# motherboard.net
KiCad netlist of a schematic drawn in EAGLE
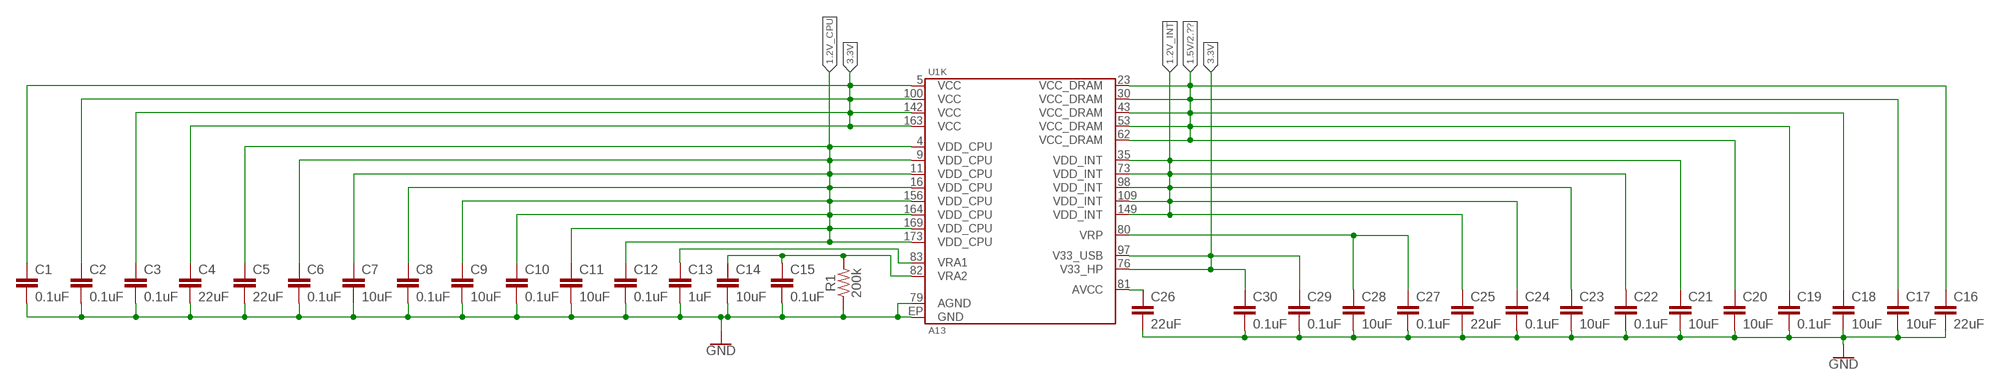
[diagram p0: schematic, sheet 1]
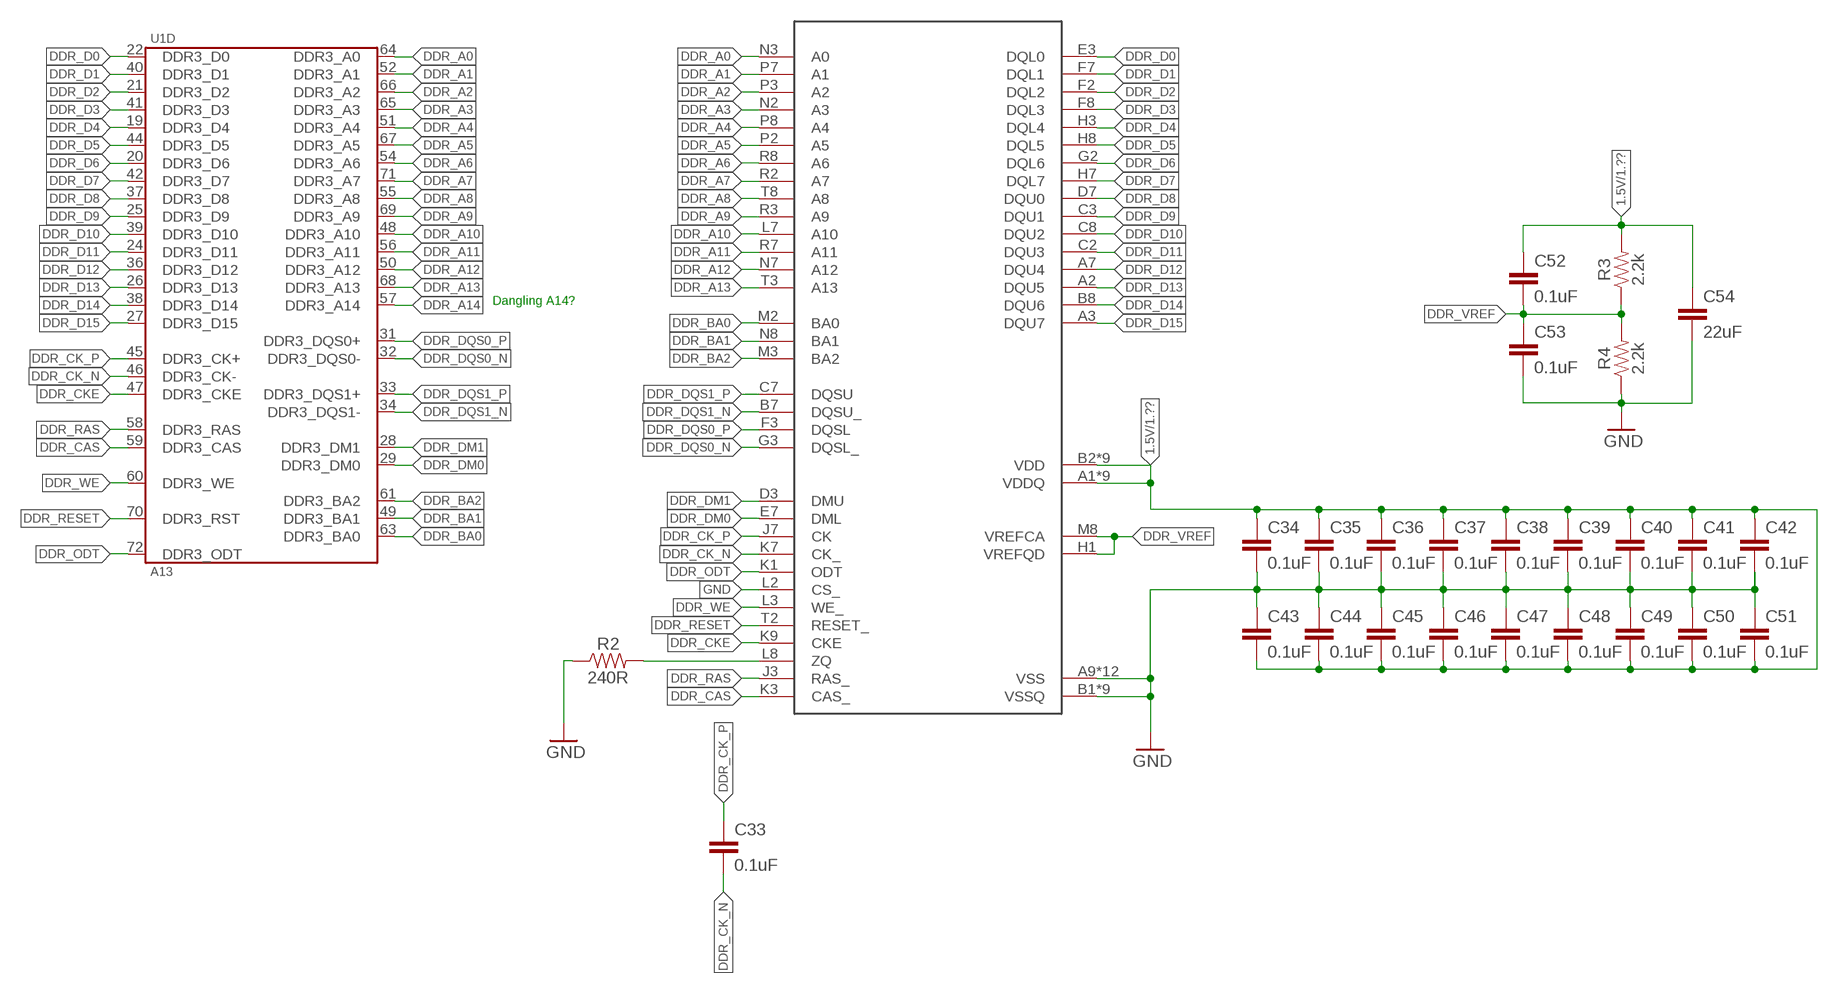
[diagram p1: schematic, sheet 2]
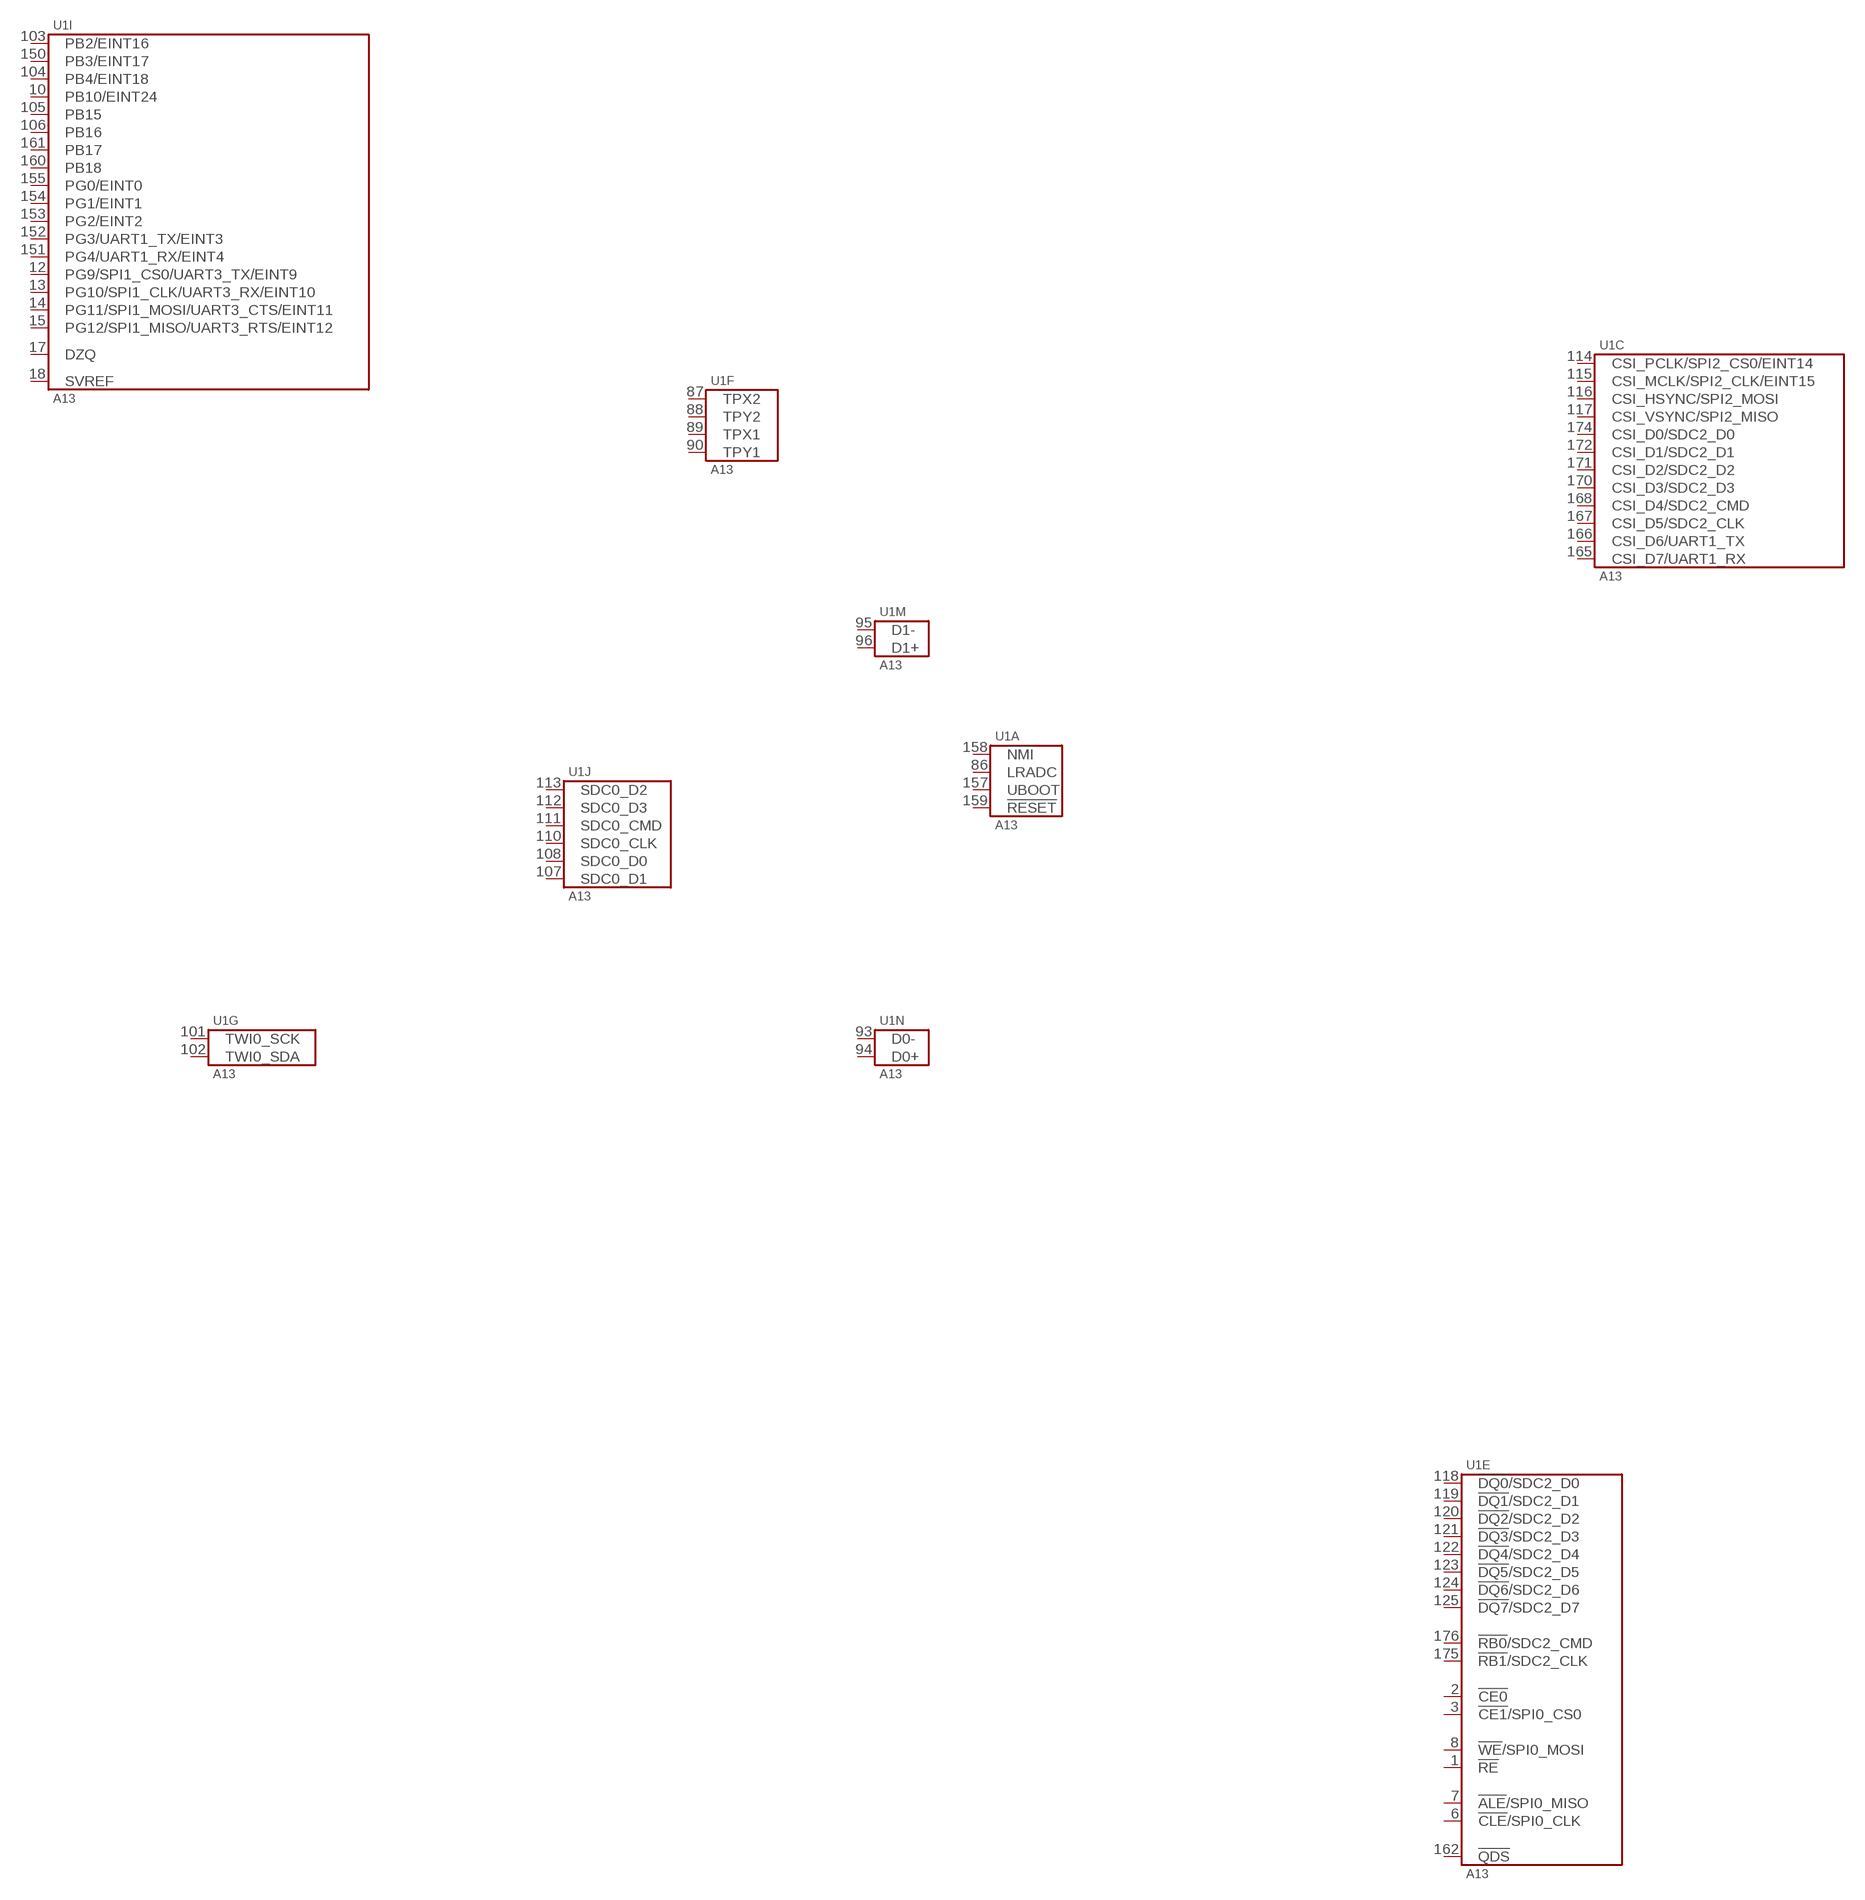
[diagram p2: schematic, sheet 5]
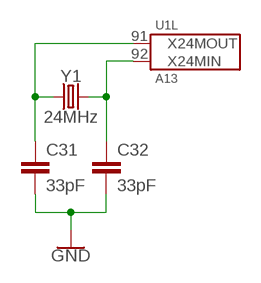
[diagram p3: schematic, sheet 6]

(export (version "E")
  (design (tool "Eeschema 10.0.6"))
  (components
    (comp (ref "C1")
      (value "0.1uF")
      (footprint "eagle-import:0603")
      (libsource (lib "eagle-import") (part "0.1UF-0603-25V-(+80/-20%)"))
    )
    (comp (ref "C2")
      (value "0.1uF")
      (footprint "eagle-import:0603")
      (libsource (lib "eagle-import") (part "0.1UF-0603-25V-(+80/-20%)"))
    )
    (comp (ref "C3")
      (value "0.1uF")
      (footprint "eagle-import:0603")
      (libsource (lib "eagle-import") (part "0.1UF-0603-25V-(+80/-20%)"))
    )
    (comp (ref "C4")
      (value "22uF")
      (footprint "eagle-import:0603")
      (libsource (lib "eagle-import") (part "0.1UF-0603-25V-(+80/-20%)"))
    )
    (comp (ref "C5")
      (value "22uF")
      (footprint "eagle-import:0603")
      (libsource (lib "eagle-import") (part "0.1UF-0603-25V-(+80/-20%)"))
    )
    (comp (ref "C6")
      (value "0.1uF")
      (footprint "eagle-import:0603")
      (libsource (lib "eagle-import") (part "0.1UF-0603-25V-(+80/-20%)"))
    )
    (comp (ref "C7")
      (value "10uF")
      (footprint "eagle-import:0603")
      (libsource (lib "eagle-import") (part "0.1UF-0603-25V-(+80/-20%)"))
    )
    (comp (ref "C8")
      (value "0.1uF")
      (footprint "eagle-import:0603")
      (libsource (lib "eagle-import") (part "0.1UF-0603-25V-(+80/-20%)"))
    )
    (comp (ref "C9")
      (value "10uF")
      (footprint "eagle-import:0603")
      (libsource (lib "eagle-import") (part "0.1UF-0603-25V-(+80/-20%)"))
    )
    (comp (ref "C10")
      (value "0.1uF")
      (footprint "eagle-import:0603")
      (libsource (lib "eagle-import") (part "0.1UF-0603-25V-(+80/-20%)"))
    )
    (comp (ref "C11")
      (value "10uF")
      (footprint "eagle-import:0603")
      (libsource (lib "eagle-import") (part "0.1UF-0603-25V-(+80/-20%)"))
    )
    (comp (ref "C12")
      (value "0.1uF")
      (footprint "eagle-import:0603")
      (libsource (lib "eagle-import") (part "0.1UF-0603-25V-(+80/-20%)"))
    )
    (comp (ref "C13")
      (value "1uF")
      (footprint "eagle-import:0603")
      (libsource (lib "eagle-import") (part "0.1UF-0603-25V-(+80/-20%)"))
    )
    (comp (ref "C14")
      (value "10uF")
      (footprint "eagle-import:0603")
      (libsource (lib "eagle-import") (part "0.1UF-0603-25V-(+80/-20%)"))
    )
    (comp (ref "C15")
      (value "0.1uF")
      (footprint "eagle-import:0603")
      (libsource (lib "eagle-import") (part "0.1UF-0603-25V-(+80/-20%)"))
    )
    (comp (ref "C16")
      (value "22uF")
      (footprint "eagle-import:0603")
      (libsource (lib "eagle-import") (part "0.1UF-0603-25V-(+80/-20%)"))
    )
    (comp (ref "C17")
      (value "10uF")
      (footprint "eagle-import:0603")
      (libsource (lib "eagle-import") (part "0.1UF-0603-25V-(+80/-20%)"))
    )
    (comp (ref "C18")
      (value "10uF")
      (footprint "eagle-import:0603")
      (libsource (lib "eagle-import") (part "0.1UF-0603-25V-(+80/-20%)"))
    )
    (comp (ref "C19")
      (value "0.1uF")
      (footprint "eagle-import:0603")
      (libsource (lib "eagle-import") (part "0.1UF-0603-25V-(+80/-20%)"))
    )
    (comp (ref "C20")
      (value "10uF")
      (footprint "eagle-import:0603")
      (libsource (lib "eagle-import") (part "0.1UF-0603-25V-(+80/-20%)"))
    )
    (comp (ref "C21")
      (value "10uF")
      (footprint "eagle-import:0603")
      (libsource (lib "eagle-import") (part "0.1UF-0603-25V-(+80/-20%)"))
    )
    (comp (ref "C22")
      (value "0.1uF")
      (footprint "eagle-import:0603")
      (libsource (lib "eagle-import") (part "0.1UF-0603-25V-(+80/-20%)"))
    )
    (comp (ref "C23")
      (value "10uF")
      (footprint "eagle-import:0603")
      (libsource (lib "eagle-import") (part "0.1UF-0603-25V-(+80/-20%)"))
    )
    (comp (ref "C24")
      (value "0.1uF")
      (footprint "eagle-import:0603")
      (libsource (lib "eagle-import") (part "0.1UF-0603-25V-(+80/-20%)"))
    )
    (comp (ref "C25")
      (value "22uF")
      (footprint "eagle-import:0603")
      (libsource (lib "eagle-import") (part "0.1UF-0603-25V-(+80/-20%)"))
    )
    (comp (ref "C26")
      (value "22uF")
      (footprint "eagle-import:0603")
      (libsource (lib "eagle-import") (part "0.1UF-0603-25V-(+80/-20%)"))
    )
    (comp (ref "C27")
      (value "0.1uF")
      (footprint "eagle-import:0603")
      (libsource (lib "eagle-import") (part "0.1UF-0603-25V-(+80/-20%)"))
    )
    (comp (ref "C28")
      (value "10uF")
      (footprint "eagle-import:0603")
      (libsource (lib "eagle-import") (part "0.1UF-0603-25V-(+80/-20%)"))
    )
    (comp (ref "C29")
      (value "0.1uF")
      (footprint "eagle-import:0603")
      (libsource (lib "eagle-import") (part "0.1UF-0603-25V-(+80/-20%)"))
    )
    (comp (ref "C30")
      (value "0.1uF")
      (footprint "eagle-import:0603")
      (libsource (lib "eagle-import") (part "0.1UF-0603-25V-(+80/-20%)"))
    )
    (comp (ref "R1")
      (value "200k")
      (footprint "eagle-import:0603")
      (libsource (lib "eagle-import") (part "200KOHM-0603-1/10W-1%"))
    )
    (comp (ref "U1")
      (value "A13")
      (footprint "eagle-import:A13")
      (libsource (lib "eagle-import") (part "A13"))
    )
    (comp (ref "C33")
      (value "0.1uF")
      (footprint "eagle-import:0603")
      (libsource (lib "eagle-import") (part "0.1UF-0603-25V-(+80/-20%)"))
    )
    (comp (ref "C34")
      (value "0.1uF")
      (footprint "eagle-import:0603")
      (libsource (lib "eagle-import") (part "0.1UF-0603-25V-(+80/-20%)"))
    )
    (comp (ref "C35")
      (value "0.1uF")
      (footprint "eagle-import:0603")
      (libsource (lib "eagle-import") (part "0.1UF-0603-25V-(+80/-20%)"))
    )
    (comp (ref "C36")
      (value "0.1uF")
      (footprint "eagle-import:0603")
      (libsource (lib "eagle-import") (part "0.1UF-0603-25V-(+80/-20%)"))
    )
    (comp (ref "C37")
      (value "0.1uF")
      (footprint "eagle-import:0603")
      (libsource (lib "eagle-import") (part "0.1UF-0603-25V-(+80/-20%)"))
    )
    (comp (ref "C38")
      (value "0.1uF")
      (footprint "eagle-import:0603")
      (libsource (lib "eagle-import") (part "0.1UF-0603-25V-(+80/-20%)"))
    )
    (comp (ref "C39")
      (value "0.1uF")
      (footprint "eagle-import:0603")
      (libsource (lib "eagle-import") (part "0.1UF-0603-25V-(+80/-20%)"))
    )
    (comp (ref "C40")
      (value "0.1uF")
      (footprint "eagle-import:0603")
      (libsource (lib "eagle-import") (part "0.1UF-0603-25V-(+80/-20%)"))
    )
    (comp (ref "C41")
      (value "0.1uF")
      (footprint "eagle-import:0603")
      (libsource (lib "eagle-import") (part "0.1UF-0603-25V-(+80/-20%)"))
    )
    (comp (ref "C42")
      (value "0.1uF")
      (footprint "eagle-import:0603")
      (libsource (lib "eagle-import") (part "0.1UF-0603-25V-(+80/-20%)"))
    )
    (comp (ref "C43")
      (value "0.1uF")
      (footprint "eagle-import:0603")
      (libsource (lib "eagle-import") (part "0.1UF-0603-25V-(+80/-20%)"))
    )
    (comp (ref "C44")
      (value "0.1uF")
      (footprint "eagle-import:0603")
      (libsource (lib "eagle-import") (part "0.1UF-0603-25V-(+80/-20%)"))
    )
    (comp (ref "C45")
      (value "0.1uF")
      (footprint "eagle-import:0603")
      (libsource (lib "eagle-import") (part "0.1UF-0603-25V-(+80/-20%)"))
    )
    (comp (ref "C46")
      (value "0.1uF")
      (footprint "eagle-import:0603")
      (libsource (lib "eagle-import") (part "0.1UF-0603-25V-(+80/-20%)"))
    )
    (comp (ref "C47")
      (value "0.1uF")
      (footprint "eagle-import:0603")
      (libsource (lib "eagle-import") (part "0.1UF-0603-25V-(+80/-20%)"))
    )
    (comp (ref "C48")
      (value "0.1uF")
      (footprint "eagle-import:0603")
      (libsource (lib "eagle-import") (part "0.1UF-0603-25V-(+80/-20%)"))
    )
    (comp (ref "C49")
      (value "0.1uF")
      (footprint "eagle-import:0603")
      (libsource (lib "eagle-import") (part "0.1UF-0603-25V-(+80/-20%)"))
    )
    (comp (ref "C50")
      (value "0.1uF")
      (footprint "eagle-import:0603")
      (libsource (lib "eagle-import") (part "0.1UF-0603-25V-(+80/-20%)"))
    )
    (comp (ref "C51")
      (value "0.1uF")
      (footprint "eagle-import:0603")
      (libsource (lib "eagle-import") (part "0.1UF-0603-25V-(+80/-20%)"))
    )
    (comp (ref "C52")
      (value "0.1uF")
      (footprint "eagle-import:0603")
      (libsource (lib "eagle-import") (part "0.1UF-0603-25V-(+80/-20%)"))
    )
    (comp (ref "C53")
      (value "0.1uF")
      (footprint "eagle-import:0603")
      (libsource (lib "eagle-import") (part "0.1UF-0603-25V-(+80/-20%)"))
    )
    (comp (ref "C54")
      (value "22uF")
      (footprint "eagle-import:0603")
      (libsource (lib "eagle-import") (part "0.1UF-0603-25V-(+80/-20%)"))
    )
    (comp (ref "DRAM")
      (value "AS4C128M16D3B-12BCN")
      (footprint "eagle-import:FBGA96-6X16")
      (libsource (lib "eagle-import") (part "AS4C128M16D3B-12BCN"))
    )
    (comp (ref "R2")
      (value "240R")
      (footprint "eagle-import:0603")
      (libsource (lib "eagle-import") (part "200KOHM-0603-1/10W-1%"))
    )
    (comp (ref "R3")
      (value "2.2k")
      (footprint "eagle-import:0603")
      (libsource (lib "eagle-import") (part "200KOHM-0603-1/10W-1%"))
    )
    (comp (ref "R4")
      (value "2.2k")
      (footprint "eagle-import:0603")
      (libsource (lib "eagle-import") (part "200KOHM-0603-1/10W-1%"))
    )
    (comp (ref "C31")
      (value "33pF")
      (footprint "eagle-import:0603")
      (libsource (lib "eagle-import") (part "0.1UF-0603-25V-(+80/-20%)"))
    )
    (comp (ref "C32")
      (value "33pF")
      (footprint "eagle-import:0603")
      (libsource (lib "eagle-import") (part "0.1UF-0603-25V-(+80/-20%)"))
    )
    (comp (ref "Y1")
      (value "24MHz")
      (footprint "eagle-import:CRYSTAL-SMD-5X3.2-4PAD")
      (libsource (lib "eagle-import") (part "CRYSTAL-24MHZ{dblquote}"))
    )
  )
  (nets
    (net (code "1") (name "1.2V_CPU") (class "Default")
      (node (ref "C10") (pin "1") (pinfunction "1_1") (pintype "passive"))
      (node (ref "C11") (pin "1") (pinfunction "1_1") (pintype "passive"))
      (node (ref "C12") (pin "1") (pinfunction "1_1") (pintype "passive"))
      (node (ref "C5") (pin "1") (pinfunction "1_1") (pintype "passive"))
      (node (ref "C6") (pin "1") (pinfunction "1_1") (pintype "passive"))
      (node (ref "C7") (pin "1") (pinfunction "1_1") (pintype "passive"))
      (node (ref "C8") (pin "1") (pinfunction "1_1") (pintype "passive"))
      (node (ref "C9") (pin "1") (pinfunction "1_1") (pintype "passive"))
      (node (ref "U1") (pin "11") (pinfunction "VDD_CPU_11") (pintype "bidirectional"))
      (node (ref "U1") (pin "156") (pinfunction "VDD_CPU_156") (pintype "bidirectional"))
      (node (ref "U1") (pin "16") (pinfunction "VDD_CPU_16") (pintype "bidirectional"))
      (node (ref "U1") (pin "164") (pinfunction "VDD_CPU_164") (pintype "bidirectional"))
      (node (ref "U1") (pin "169") (pinfunction "VDD_CPU_169") (pintype "bidirectional"))
      (node (ref "U1") (pin "173") (pinfunction "VDD_CPU_173") (pintype "bidirectional"))
      (node (ref "U1") (pin "4") (pinfunction "VDD_CPU_4") (pintype "bidirectional"))
      (node (ref "U1") (pin "9") (pinfunction "VDD_CPU_9") (pintype "bidirectional"))
    )
    (net (code "2") (name "1.2V_INT") (class "Default")
      (node (ref "C21") (pin "1") (pinfunction "1_1") (pintype "passive"))
      (node (ref "C22") (pin "1") (pinfunction "1_1") (pintype "passive"))
      (node (ref "C23") (pin "1") (pinfunction "1_1") (pintype "passive"))
      (node (ref "C24") (pin "1") (pinfunction "1_1") (pintype "passive"))
      (node (ref "C25") (pin "1") (pinfunction "1_1") (pintype "passive"))
      (node (ref "U1") (pin "109") (pinfunction "VDD_INT_109") (pintype "bidirectional"))
      (node (ref "U1") (pin "149") (pinfunction "VDD_INT_149") (pintype "bidirectional"))
      (node (ref "U1") (pin "35") (pinfunction "VDD_INT_35") (pintype "bidirectional"))
      (node (ref "U1") (pin "73") (pinfunction "VDD_INT_73") (pintype "bidirectional"))
      (node (ref "U1") (pin "98") (pinfunction "VDD_INT_98") (pintype "bidirectional"))
    )
    (net (code "3") (name "1.5V") (class "Default")
      (node (ref "C16") (pin "1") (pinfunction "1_1") (pintype "passive"))
      (node (ref "C17") (pin "1") (pinfunction "1_1") (pintype "passive"))
      (node (ref "C18") (pin "1") (pinfunction "1_1") (pintype "passive"))
      (node (ref "C19") (pin "1") (pinfunction "1_1") (pintype "passive"))
      (node (ref "C20") (pin "1") (pinfunction "1_1") (pintype "passive"))
      (node (ref "C34") (pin "1") (pinfunction "1_1") (pintype "passive"))
      (node (ref "C35") (pin "1") (pinfunction "1_1") (pintype "passive"))
      (node (ref "C36") (pin "1") (pinfunction "1_1") (pintype "passive"))
      (node (ref "C37") (pin "1") (pinfunction "1_1") (pintype "passive"))
      (node (ref "C38") (pin "1") (pinfunction "1_1") (pintype "passive"))
      (node (ref "C39") (pin "1") (pinfunction "1_1") (pintype "passive"))
      (node (ref "C40") (pin "1") (pinfunction "1_1") (pintype "passive"))
      (node (ref "C41") (pin "1") (pinfunction "1_1") (pintype "passive"))
      (node (ref "C42") (pin "1") (pinfunction "1_1") (pintype "passive"))
      (node (ref "C43") (pin "2") (pinfunction "2_2") (pintype "passive"))
      (node (ref "C44") (pin "2") (pinfunction "2_2") (pintype "passive"))
      (node (ref "C45") (pin "2") (pinfunction "2_2") (pintype "passive"))
      (node (ref "C46") (pin "2") (pinfunction "2_2") (pintype "passive"))
      (node (ref "C47") (pin "2") (pinfunction "2_2") (pintype "passive"))
      (node (ref "C48") (pin "2") (pinfunction "2_2") (pintype "passive"))
      (node (ref "C49") (pin "2") (pinfunction "2_2") (pintype "passive"))
      (node (ref "C50") (pin "2") (pinfunction "2_2") (pintype "passive"))
      (node (ref "C51") (pin "2") (pinfunction "2_2") (pintype "passive"))
      (node (ref "C52") (pin "1") (pinfunction "1_1") (pintype "passive"))
      (node (ref "C54") (pin "1") (pinfunction "1_1") (pintype "passive"))
      (node (ref "DRAM") (pin "A1") (pinfunction "VDDQ_A1") (pintype "bidirectional"))
      (node (ref "DRAM") (pin "A8") (pinfunction "VDDQ_A8") (pintype "bidirectional"))
      (node (ref "DRAM") (pin "B2") (pinfunction "VDD_B2") (pintype "bidirectional"))
      (node (ref "DRAM") (pin "C1") (pinfunction "VDDQ_C1") (pintype "bidirectional"))
      (node (ref "DRAM") (pin "C9") (pinfunction "VDDQ_C9") (pintype "bidirectional"))
      (node (ref "DRAM") (pin "D2") (pinfunction "VDDQ_D2") (pintype "bidirectional"))
      (node (ref "DRAM") (pin "D9") (pinfunction "VDD_D9") (pintype "bidirectional"))
      (node (ref "DRAM") (pin "E9") (pinfunction "VDDQ_E9") (pintype "bidirectional"))
      (node (ref "DRAM") (pin "F1") (pinfunction "VDDQ_F1") (pintype "bidirectional"))
      (node (ref "DRAM") (pin "G7") (pinfunction "VDD_G7") (pintype "bidirectional"))
      (node (ref "DRAM") (pin "H2") (pinfunction "VDDQ_H2") (pintype "bidirectional"))
      (node (ref "DRAM") (pin "H9") (pinfunction "VDDQ_H9") (pintype "bidirectional"))
      (node (ref "DRAM") (pin "K2") (pinfunction "VDD_K2") (pintype "bidirectional"))
      (node (ref "DRAM") (pin "K8") (pinfunction "VDD_K8") (pintype "bidirectional"))
      (node (ref "DRAM") (pin "N1") (pinfunction "VDD_N1") (pintype "bidirectional"))
      (node (ref "DRAM") (pin "N9") (pinfunction "VDD_N9") (pintype "bidirectional"))
      (node (ref "DRAM") (pin "R1") (pinfunction "VDD_R1") (pintype "bidirectional"))
      (node (ref "DRAM") (pin "R9") (pinfunction "VDD_R9") (pintype "bidirectional"))
      (node (ref "R3") (pin "2") (pinfunction "2_2") (pintype "passive"))
      (node (ref "U1") (pin "23") (pinfunction "VCC_DRAM_23") (pintype "bidirectional"))
      (node (ref "U1") (pin "30") (pinfunction "VCC_DRAM_30") (pintype "bidirectional"))
      (node (ref "U1") (pin "43") (pinfunction "VCC_DRAM_43") (pintype "bidirectional"))
      (node (ref "U1") (pin "53") (pinfunction "VCC_DRAM_53") (pintype "bidirectional"))
      (node (ref "U1") (pin "62") (pinfunction "VCC_DRAM_62") (pintype "bidirectional"))
    )
    (net (code "4") (name "3.3V") (class "Default")
      (node (ref "C1") (pin "1") (pinfunction "1_1") (pintype "passive"))
      (node (ref "C2") (pin "1") (pinfunction "1_1") (pintype "passive"))
      (node (ref "C29") (pin "1") (pinfunction "1_1") (pintype "passive"))
      (node (ref "C3") (pin "1") (pinfunction "1_1") (pintype "passive"))
      (node (ref "C30") (pin "1") (pinfunction "1_1") (pintype "passive"))
      (node (ref "C4") (pin "1") (pinfunction "1_1") (pintype "passive"))
      (node (ref "U1") (pin "100") (pinfunction "VCC_100") (pintype "bidirectional"))
      (node (ref "U1") (pin "142") (pinfunction "VCC_142") (pintype "bidirectional"))
      (node (ref "U1") (pin "163") (pinfunction "VCC_163") (pintype "bidirectional"))
      (node (ref "U1") (pin "5") (pinfunction "VCC_5") (pintype "bidirectional"))
      (node (ref "U1") (pin "76") (pinfunction "V33_HP_76") (pintype "bidirectional"))
      (node (ref "U1") (pin "97") (pinfunction "V33_USB_97") (pintype "bidirectional"))
    )
    (net (code "5") (name "DDR_A0") (class "Default")
      (node (ref "DRAM") (pin "N3") (pinfunction "A0_N3") (pintype "bidirectional"))
      (node (ref "U1") (pin "64") (pinfunction "DDR3_A0_64") (pintype "bidirectional"))
    )
    (net (code "6") (name "DDR_A1") (class "Default")
      (node (ref "DRAM") (pin "P7") (pinfunction "A1_P7") (pintype "bidirectional"))
      (node (ref "U1") (pin "52") (pinfunction "DDR3_A1_52") (pintype "bidirectional"))
    )
    (net (code "7") (name "DDR_A2") (class "Default")
      (node (ref "DRAM") (pin "P3") (pinfunction "A2_P3") (pintype "bidirectional"))
      (node (ref "U1") (pin "66") (pinfunction "DDR3_A2_66") (pintype "bidirectional"))
    )
    (net (code "8") (name "DDR_A3") (class "Default")
      (node (ref "DRAM") (pin "N2") (pinfunction "A3_N2") (pintype "bidirectional"))
      (node (ref "U1") (pin "65") (pinfunction "DDR3_A3_65") (pintype "bidirectional"))
    )
    (net (code "9") (name "DDR_A4") (class "Default")
      (node (ref "DRAM") (pin "P8") (pinfunction "A4_P8") (pintype "bidirectional"))
      (node (ref "U1") (pin "51") (pinfunction "DDR3_A4_51") (pintype "bidirectional"))
    )
    (net (code "10") (name "DDR_A5") (class "Default")
      (node (ref "DRAM") (pin "P2") (pinfunction "A5_P2") (pintype "bidirectional"))
      (node (ref "U1") (pin "67") (pinfunction "DDR3_A5_67") (pintype "bidirectional"))
    )
    (net (code "11") (name "DDR_A6") (class "Default")
      (node (ref "DRAM") (pin "R8") (pinfunction "A6_R8") (pintype "bidirectional"))
      (node (ref "U1") (pin "54") (pinfunction "DDR3_A6_54") (pintype "bidirectional"))
    )
    (net (code "12") (name "DDR_A7") (class "Default")
      (node (ref "DRAM") (pin "R2") (pinfunction "A7_R2") (pintype "bidirectional"))
      (node (ref "U1") (pin "71") (pinfunction "DDR3_A7_71") (pintype "bidirectional"))
    )
    (net (code "13") (name "DDR_A8") (class "Default")
      (node (ref "DRAM") (pin "T8") (pinfunction "A8_T8") (pintype "bidirectional"))
      (node (ref "U1") (pin "55") (pinfunction "DDR3_A8_55") (pintype "bidirectional"))
    )
    (net (code "14") (name "DDR_A9") (class "Default")
      (node (ref "DRAM") (pin "R3") (pinfunction "A9_R3") (pintype "bidirectional"))
      (node (ref "U1") (pin "69") (pinfunction "DDR3_A9_69") (pintype "bidirectional"))
    )
    (net (code "15") (name "DDR_A10") (class "Default")
      (node (ref "DRAM") (pin "L7") (pinfunction "A10_L7") (pintype "bidirectional"))
      (node (ref "U1") (pin "48") (pinfunction "DDR3_A10_48") (pintype "bidirectional"))
    )
    (net (code "16") (name "DDR_A11") (class "Default")
      (node (ref "DRAM") (pin "R7") (pinfunction "A11_R7") (pintype "bidirectional"))
      (node (ref "U1") (pin "56") (pinfunction "DDR3_A11_56") (pintype "bidirectional"))
    )
    (net (code "17") (name "DDR_A12") (class "Default")
      (node (ref "DRAM") (pin "N7") (pinfunction "A12_N7") (pintype "bidirectional"))
      (node (ref "U1") (pin "50") (pinfunction "DDR3_A12_50") (pintype "bidirectional"))
    )
    (net (code "18") (name "DDR_A13") (class "Default")
      (node (ref "DRAM") (pin "T3") (pinfunction "A13_T3") (pintype "bidirectional"))
      (node (ref "U1") (pin "68") (pinfunction "DDR3_A13_68") (pintype "bidirectional"))
    )
    (net (code "19") (name "DDR_A14") (class "Default")
      (node (ref "U1") (pin "57") (pinfunction "DDR3_A14_57") (pintype "bidirectional"))
    )
    (net (code "20") (name "DDR_BA0") (class "Default")
      (node (ref "DRAM") (pin "M2") (pinfunction "BA0_M2") (pintype "bidirectional"))
      (node (ref "U1") (pin "63") (pinfunction "DDR3_BA0_63") (pintype "bidirectional"))
    )
    (net (code "21") (name "DDR_BA1") (class "Default")
      (node (ref "DRAM") (pin "N8") (pinfunction "BA1_N8") (pintype "bidirectional"))
      (node (ref "U1") (pin "49") (pinfunction "DDR3_BA1_49") (pintype "bidirectional"))
    )
    (net (code "22") (name "DDR_BA2") (class "Default")
      (node (ref "DRAM") (pin "M3") (pinfunction "BA2_M3") (pintype "bidirectional"))
      (node (ref "U1") (pin "61") (pinfunction "DDR3_BA2_61") (pintype "bidirectional"))
    )
    (net (code "23") (name "DDR_CAS") (class "Default")
      (node (ref "DRAM") (pin "K3") (pinfunction "CAS__K3") (pintype "bidirectional"))
      (node (ref "U1") (pin "59") (pinfunction "DDR3_CAS_59") (pintype "bidirectional"))
    )
    (net (code "24") (name "DDR_CKE") (class "Default")
      (node (ref "DRAM") (pin "K9") (pinfunction "CKE_K9") (pintype "bidirectional"))
      (node (ref "U1") (pin "47") (pinfunction "DDR3_CKE_47") (pintype "bidirectional"))
    )
    (net (code "25") (name "DDR_CK_N") (class "Default")
      (node (ref "C33") (pin "2") (pinfunction "2_2") (pintype "passive"))
      (node (ref "DRAM") (pin "K7") (pinfunction "CK__K7") (pintype "bidirectional"))
      (node (ref "U1") (pin "46") (pinfunction "DDR3_CK-_46") (pintype "bidirectional"))
    )
    (net (code "26") (name "DDR_CK_P") (class "Default")
      (node (ref "C33") (pin "1") (pinfunction "1_1") (pintype "passive"))
      (node (ref "DRAM") (pin "J7") (pinfunction "CK_J7") (pintype "bidirectional"))
      (node (ref "U1") (pin "45") (pinfunction "DDR3_CK+_45") (pintype "bidirectional"))
    )
    (net (code "27") (name "DDR_D0") (class "Default")
      (node (ref "DRAM") (pin "E3") (pinfunction "DQL0_E3") (pintype "bidirectional"))
      (node (ref "U1") (pin "22") (pinfunction "DDR3_D0_22") (pintype "bidirectional"))
    )
    (net (code "28") (name "DDR_D1") (class "Default")
      (node (ref "DRAM") (pin "F7") (pinfunction "DQL1_F7") (pintype "bidirectional"))
      (node (ref "U1") (pin "40") (pinfunction "DDR3_D1_40") (pintype "bidirectional"))
    )
    (net (code "29") (name "DDR_D2") (class "Default")
      (node (ref "DRAM") (pin "F2") (pinfunction "DQL2_F2") (pintype "bidirectional"))
      (node (ref "U1") (pin "21") (pinfunction "DDR3_D2_21") (pintype "bidirectional"))
    )
    (net (code "30") (name "DDR_D3") (class "Default")
      (node (ref "DRAM") (pin "F8") (pinfunction "DQL3_F8") (pintype "bidirectional"))
      (node (ref "U1") (pin "41") (pinfunction "DDR3_D3_41") (pintype "bidirectional"))
    )
    (net (code "31") (name "DDR_D4") (class "Default")
      (node (ref "DRAM") (pin "H3") (pinfunction "DQL4_H3") (pintype "bidirectional"))
      (node (ref "U1") (pin "19") (pinfunction "DDR3_D4_19") (pintype "bidirectional"))
    )
    (net (code "32") (name "DDR_D5") (class "Default")
      (node (ref "DRAM") (pin "H8") (pinfunction "DQL5_H8") (pintype "bidirectional"))
      (node (ref "U1") (pin "44") (pinfunction "DDR3_D5_44") (pintype "bidirectional"))
    )
    (net (code "33") (name "DDR_D6") (class "Default")
      (node (ref "DRAM") (pin "G2") (pinfunction "DQL6_G2") (pintype "bidirectional"))
      (node (ref "U1") (pin "20") (pinfunction "DDR3_D6_20") (pintype "bidirectional"))
    )
    (net (code "34") (name "DDR_D7") (class "Default")
      (node (ref "DRAM") (pin "H7") (pinfunction "DQL7_H7") (pintype "bidirectional"))
      (node (ref "U1") (pin "42") (pinfunction "DDR3_D7_42") (pintype "bidirectional"))
    )
    (net (code "35") (name "DDR_D8") (class "Default")
      (node (ref "DRAM") (pin "D7") (pinfunction "DQU0_D7") (pintype "bidirectional"))
      (node (ref "U1") (pin "37") (pinfunction "DDR3_D8_37") (pintype "bidirectional"))
    )
    (net (code "36") (name "DDR_D9") (class "Default")
      (node (ref "DRAM") (pin "C3") (pinfunction "DQU1_C3") (pintype "bidirectional"))
      (node (ref "U1") (pin "25") (pinfunction "DDR3_D9_25") (pintype "bidirectional"))
    )
    (net (code "37") (name "DDR_D10") (class "Default")
      (node (ref "DRAM") (pin "C8") (pinfunction "DQU2_C8") (pintype "bidirectional"))
      (node (ref "U1") (pin "39") (pinfunction "DDR3_D10_39") (pintype "bidirectional"))
    )
    (net (code "38") (name "DDR_D11") (class "Default")
      (node (ref "DRAM") (pin "C2") (pinfunction "DQU3_C2") (pintype "bidirectional"))
      (node (ref "U1") (pin "24") (pinfunction "DDR3_D11_24") (pintype "bidirectional"))
    )
    (net (code "39") (name "DDR_D12") (class "Default")
      (node (ref "DRAM") (pin "A7") (pinfunction "DQU4_A7") (pintype "bidirectional"))
      (node (ref "U1") (pin "36") (pinfunction "DDR3_D12_36") (pintype "bidirectional"))
    )
    (net (code "40") (name "DDR_D13") (class "Default")
      (node (ref "DRAM") (pin "A2") (pinfunction "DQU5_A2") (pintype "bidirectional"))
      (node (ref "U1") (pin "26") (pinfunction "DDR3_D13_26") (pintype "bidirectional"))
    )
    (net (code "41") (name "DDR_D14") (class "Default")
      (node (ref "DRAM") (pin "B8") (pinfunction "DQU6_B8") (pintype "bidirectional"))
      (node (ref "U1") (pin "38") (pinfunction "DDR3_D14_38") (pintype "bidirectional"))
    )
    (net (code "42") (name "DDR_D15") (class "Default")
      (node (ref "DRAM") (pin "A3") (pinfunction "DQU7_A3") (pintype "bidirectional"))
      (node (ref "U1") (pin "27") (pinfunction "DDR3_D15_27") (pintype "bidirectional"))
    )
    (net (code "43") (name "DDR_DM0") (class "Default")
      (node (ref "DRAM") (pin "E7") (pinfunction "DML_E7") (pintype "bidirectional"))
      (node (ref "U1") (pin "29") (pinfunction "DDR3_DM0_29") (pintype "bidirectional"))
    )
    (net (code "44") (name "DDR_DM1") (class "Default")
      (node (ref "DRAM") (pin "D3") (pinfunction "DMU_D3") (pintype "bidirectional"))
      (node (ref "U1") (pin "28") (pinfunction "DDR3_DM1_28") (pintype "bidirectional"))
    )
    (net (code "45") (name "DDR_DQS0_N") (class "Default")
      (node (ref "DRAM") (pin "G3") (pinfunction "DQSL__G3") (pintype "bidirectional"))
      (node (ref "U1") (pin "32") (pinfunction "DDR3_DQS0-_32") (pintype "bidirectional"))
    )
    (net (code "46") (name "DDR_DQS0_P") (class "Default")
      (node (ref "DRAM") (pin "F3") (pinfunction "DQSL_F3") (pintype "bidirectional"))
      (node (ref "U1") (pin "31") (pinfunction "DDR3_DQS0+_31") (pintype "bidirectional"))
    )
    (net (code "47") (name "DDR_DQS1_N") (class "Default")
      (node (ref "DRAM") (pin "B7") (pinfunction "DQSU__B7") (pintype "bidirectional"))
      (node (ref "U1") (pin "34") (pinfunction "DDR3_DQS1-_34") (pintype "bidirectional"))
    )
    (net (code "48") (name "DDR_DQS1_P") (class "Default")
      (node (ref "DRAM") (pin "C7") (pinfunction "DQSU_C7") (pintype "bidirectional"))
      (node (ref "U1") (pin "33") (pinfunction "DDR3_DQS1+_33") (pintype "bidirectional"))
    )
    (net (code "49") (name "DDR_ODT") (class "Default")
      (node (ref "DRAM") (pin "K1") (pinfunction "ODT_K1") (pintype "bidirectional"))
      (node (ref "U1") (pin "72") (pinfunction "DDR3_ODT_72") (pintype "bidirectional"))
    )
    (net (code "50") (name "DDR_RAS") (class "Default")
      (node (ref "DRAM") (pin "J3") (pinfunction "RAS__J3") (pintype "bidirectional"))
      (node (ref "U1") (pin "58") (pinfunction "DDR3_RAS_58") (pintype "bidirectional"))
    )
    (net (code "51") (name "DDR_RESET") (class "Default")
      (node (ref "DRAM") (pin "T2") (pinfunction "RESET__T2") (pintype "bidirectional"))
      (node (ref "U1") (pin "70") (pinfunction "DDR3_RST_70") (pintype "bidirectional"))
    )
    (net (code "52") (name "DDR_VREF") (class "Default")
      (node (ref "C52") (pin "2") (pinfunction "2_2") (pintype "passive"))
      (node (ref "C53") (pin "1") (pinfunction "1_1") (pintype "passive"))
      (node (ref "DRAM") (pin "H1") (pinfunction "VREFQD_H1") (pintype "bidirectional"))
      (node (ref "DRAM") (pin "M8") (pinfunction "VREFCA_M8") (pintype "bidirectional"))
      (node (ref "R3") (pin "1") (pinfunction "1_1") (pintype "passive"))
      (node (ref "R4") (pin "2") (pinfunction "2_2") (pintype "passive"))
    )
    (net (code "53") (name "DDR_WE") (class "Default")
      (node (ref "DRAM") (pin "L3") (pinfunction "WE__L3") (pintype "bidirectional"))
      (node (ref "U1") (pin "60") (pinfunction "DDR3_WE_60") (pintype "bidirectional"))
    )
    (net (code "54") (name "GND") (class "Default")
      (node (ref "C1") (pin "2") (pinfunction "2_2") (pintype "passive"))
      (node (ref "C10") (pin "2") (pinfunction "2_2") (pintype "passive"))
      (node (ref "C11") (pin "2") (pinfunction "2_2") (pintype "passive"))
      (node (ref "C12") (pin "2") (pinfunction "2_2") (pintype "passive"))
      (node (ref "C13") (pin "2") (pinfunction "2_2") (pintype "passive"))
      (node (ref "C14") (pin "2") (pinfunction "2_2") (pintype "passive"))
      (node (ref "C15") (pin "2") (pinfunction "2_2") (pintype "passive"))
      (node (ref "C16") (pin "2") (pinfunction "2_2") (pintype "passive"))
      (node (ref "C17") (pin "2") (pinfunction "2_2") (pintype "passive"))
      (node (ref "C18") (pin "2") (pinfunction "2_2") (pintype "passive"))
      (node (ref "C19") (pin "2") (pinfunction "2_2") (pintype "passive"))
      (node (ref "C2") (pin "2") (pinfunction "2_2") (pintype "passive"))
      (node (ref "C20") (pin "2") (pinfunction "2_2") (pintype "passive"))
      (node (ref "C21") (pin "2") (pinfunction "2_2") (pintype "passive"))
      (node (ref "C22") (pin "2") (pinfunction "2_2") (pintype "passive"))
      (node (ref "C23") (pin "2") (pinfunction "2_2") (pintype "passive"))
      (node (ref "C24") (pin "2") (pinfunction "2_2") (pintype "passive"))
      (node (ref "C25") (pin "2") (pinfunction "2_2") (pintype "passive"))
      (node (ref "C26") (pin "2") (pinfunction "2_2") (pintype "passive"))
      (node (ref "C27") (pin "2") (pinfunction "2_2") (pintype "passive"))
      (node (ref "C28") (pin "2") (pinfunction "2_2") (pintype "passive"))
      (node (ref "C29") (pin "2") (pinfunction "2_2") (pintype "passive"))
      (node (ref "C3") (pin "2") (pinfunction "2_2") (pintype "passive"))
      (node (ref "C30") (pin "2") (pinfunction "2_2") (pintype "passive"))
      (node (ref "C31") (pin "2") (pinfunction "2_2") (pintype "passive"))
      (node (ref "C32") (pin "2") (pinfunction "2_2") (pintype "passive"))
      (node (ref "C34") (pin "2") (pinfunction "2_2") (pintype "passive"))
      (node (ref "C35") (pin "2") (pinfunction "2_2") (pintype "passive"))
      (node (ref "C36") (pin "2") (pinfunction "2_2") (pintype "passive"))
      (node (ref "C37") (pin "2") (pinfunction "2_2") (pintype "passive"))
      (node (ref "C38") (pin "2") (pinfunction "2_2") (pintype "passive"))
      (node (ref "C39") (pin "2") (pinfunction "2_2") (pintype "passive"))
      (node (ref "C4") (pin "2") (pinfunction "2_2") (pintype "passive"))
      (node (ref "C40") (pin "2") (pinfunction "2_2") (pintype "passive"))
      (node (ref "C41") (pin "2") (pinfunction "2_2") (pintype "passive"))
      (node (ref "C42") (pin "2") (pinfunction "2_2") (pintype "passive"))
      (node (ref "C43") (pin "1") (pinfunction "1_1") (pintype "passive"))
      (node (ref "C44") (pin "1") (pinfunction "1_1") (pintype "passive"))
      (node (ref "C45") (pin "1") (pinfunction "1_1") (pintype "passive"))
      (node (ref "C46") (pin "1") (pinfunction "1_1") (pintype "passive"))
      (node (ref "C47") (pin "1") (pinfunction "1_1") (pintype "passive"))
      (node (ref "C48") (pin "1") (pinfunction "1_1") (pintype "passive"))
      (node (ref "C49") (pin "1") (pinfunction "1_1") (pintype "passive"))
      (node (ref "C5") (pin "2") (pinfunction "2_2") (pintype "passive"))
      (node (ref "C50") (pin "1") (pinfunction "1_1") (pintype "passive"))
      (node (ref "C51") (pin "1") (pinfunction "1_1") (pintype "passive"))
      (node (ref "C53") (pin "2") (pinfunction "2_2") (pintype "passive"))
      (node (ref "C54") (pin "2") (pinfunction "2_2") (pintype "passive"))
      (node (ref "C6") (pin "2") (pinfunction "2_2") (pintype "passive"))
      (node (ref "C7") (pin "2") (pinfunction "2_2") (pintype "passive"))
      (node (ref "C8") (pin "2") (pinfunction "2_2") (pintype "passive"))
      (node (ref "C9") (pin "2") (pinfunction "2_2") (pintype "passive"))
      (node (ref "DRAM") (pin "A9") (pinfunction "VSS_A9") (pintype "bidirectional"))
      (node (ref "DRAM") (pin "B1") (pinfunction "VSSQ_B1") (pintype "bidirectional"))
      (node (ref "DRAM") (pin "B3") (pinfunction "VSS_B3") (pintype "bidirectional"))
      (node (ref "DRAM") (pin "B9") (pinfunction "VSSQ_B9") (pintype "bidirectional"))
      (node (ref "DRAM") (pin "D1") (pinfunction "VSSQ_D1") (pintype "bidirectional"))
      (node (ref "DRAM") (pin "D8") (pinfunction "VSSQ_D8") (pintype "bidirectional"))
      (node (ref "DRAM") (pin "E1") (pinfunction "VSS_E1") (pintype "bidirectional"))
      (node (ref "DRAM") (pin "E2") (pinfunction "VSSQ_E2") (pintype "bidirectional"))
      (node (ref "DRAM") (pin "E8") (pinfunction "VSSQ_E8") (pintype "bidirectional"))
      (node (ref "DRAM") (pin "F9") (pinfunction "VSSQ_F9") (pintype "bidirectional"))
      (node (ref "DRAM") (pin "G1") (pinfunction "VSSQ_G1") (pintype "bidirectional"))
      (node (ref "DRAM") (pin "G8") (pinfunction "VSS_G8") (pintype "bidirectional"))
      (node (ref "DRAM") (pin "G9") (pinfunction "VSSQ_G9") (pintype "bidirectional"))
      (node (ref "DRAM") (pin "J2") (pinfunction "VSS_J2") (pintype "bidirectional"))
      (node (ref "DRAM") (pin "J8") (pinfunction "VSS_J8") (pintype "bidirectional"))
      (node (ref "DRAM") (pin "L2") (pinfunction "CS__L2") (pintype "bidirectional"))
      (node (ref "DRAM") (pin "M1") (pinfunction "VSS_M1") (pintype "bidirectional"))
      (node (ref "DRAM") (pin "M9") (pinfunction "VSS_M9") (pintype "bidirectional"))
      (node (ref "DRAM") (pin "P1") (pinfunction "VSS_P1") (pintype "bidirectional"))
      (node (ref "DRAM") (pin "P9") (pinfunction "VSS_P9") (pintype "bidirectional"))
      (node (ref "DRAM") (pin "T1") (pinfunction "VSS_T1") (pintype "bidirectional"))
      (node (ref "DRAM") (pin "T9") (pinfunction "VSS_T9") (pintype "bidirectional"))
      (node (ref "R1") (pin "1") (pinfunction "1_1") (pintype "passive"))
      (node (ref "R2") (pin "1") (pinfunction "1_1") (pintype "passive"))
      (node (ref "R4") (pin "1") (pinfunction "1_1") (pintype "passive"))
      (node (ref "U1") (pin "79") (pinfunction "AGND_79") (pintype "bidirectional"))
      (node (ref "U1") (pin "EP") (pinfunction "GND_EP") (pintype "bidirectional"))
    )
    (net (code "55") (name "Net-(DRAM-ZQ)") (class "Default")
      (node (ref "DRAM") (pin "L8") (pinfunction "ZQ_L8") (pintype "bidirectional"))
      (node (ref "R2") (pin "2") (pinfunction "2_2") (pintype "passive"))
    )
    (net (code "56") (name "Net-(U1K-AVCC)") (class "Default")
      (node (ref "C26") (pin "1") (pinfunction "1_1") (pintype "passive"))
      (node (ref "U1") (pin "81") (pinfunction "AVCC_81") (pintype "bidirectional"))
    )
    (net (code "57") (name "Net-(U1K-VRA1)") (class "Default")
      (node (ref "C13") (pin "1") (pinfunction "1_1") (pintype "passive"))
      (node (ref "U1") (pin "83") (pinfunction "VRA1_83") (pintype "bidirectional"))
    )
    (net (code "58") (name "Net-(U1K-VRA2)") (class "Default")
      (node (ref "C14") (pin "1") (pinfunction "1_1") (pintype "passive"))
      (node (ref "C15") (pin "1") (pinfunction "1_1") (pintype "passive"))
      (node (ref "R1") (pin "2") (pinfunction "2_2") (pintype "passive"))
      (node (ref "U1") (pin "82") (pinfunction "VRA2_82") (pintype "bidirectional"))
    )
    (net (code "59") (name "Net-(U1K-VRP)") (class "Default")
      (node (ref "C27") (pin "1") (pinfunction "1_1") (pintype "passive"))
      (node (ref "C28") (pin "1") (pinfunction "1_1") (pintype "passive"))
      (node (ref "U1") (pin "80") (pinfunction "VRP_80") (pintype "bidirectional"))
    )
    (net (code "60") (name "Net-(U1L-X24MIN)") (class "Default")
      (node (ref "C32") (pin "1") (pinfunction "1_1") (pintype "passive"))
      (node (ref "U1") (pin "92") (pinfunction "X24MIN_92") (pintype "bidirectional"))
      (node (ref "Y1") (pin "3") (pinfunction "2_3") (pintype "passive"))
    )
    (net (code "61") (name "Net-(U1L-X24MOUT)") (class "Default")
      (node (ref "C31") (pin "1") (pinfunction "1_1") (pintype "passive"))
      (node (ref "U1") (pin "91") (pinfunction "X24MOUT_91") (pintype "bidirectional"))
      (node (ref "Y1") (pin "1") (pinfunction "1_1") (pintype "passive"))
    )
    (net (code "62") (name "unconnected-(U1A-LRADC-Pad86)") (class "Default")
      (node (ref "U1") (pin "86") (pinfunction "LRADC_86") (pintype "bidirectional"))
    )
    (net (code "63") (name "unconnected-(U1A-UBOOT-Pad157)") (class "Default")
      (node (ref "U1") (pin "157") (pinfunction "UBOOT_157") (pintype "bidirectional"))
    )
    (net (code "64") (name "unconnected-(U1A-~{NMI}-Pad158)") (class "Default")
      (node (ref "U1") (pin "158") (pinfunction "~{NMI}_158") (pintype "bidirectional"))
    )
    (net (code "65") (name "unconnected-(U1A-~{RESET}-Pad159)") (class "Default")
      (node (ref "U1") (pin "159") (pinfunction "~{RESET}_159") (pintype "bidirectional"))
    )
    (net (code "66") (name "unconnected-(U1C-CSI_D0{slash}SDC2_D0-Pad174)") (class "Default")
      (node (ref "U1") (pin "174") (pinfunction "CSI_D0/SDC2_D0_174") (pintype "bidirectional"))
    )
    (net (code "67") (name "unconnected-(U1C-CSI_D1{slash}SDC2_D1-Pad172)") (class "Default")
      (node (ref "U1") (pin "172") (pinfunction "CSI_D1/SDC2_D1_172") (pintype "bidirectional"))
    )
    (net (code "68") (name "unconnected-(U1C-CSI_D2{slash}SDC2_D2-Pad171)") (class "Default")
      (node (ref "U1") (pin "171") (pinfunction "CSI_D2/SDC2_D2_171") (pintype "bidirectional"))
    )
    (net (code "69") (name "unconnected-(U1C-CSI_D3{slash}SDC2_D3-Pad170)") (class "Default")
      (node (ref "U1") (pin "170") (pinfunction "CSI_D3/SDC2_D3_170") (pintype "bidirectional"))
    )
    (net (code "70") (name "unconnected-(U1C-CSI_D4{slash}SDC2_CMD-Pad168)") (class "Default")
      (node (ref "U1") (pin "168") (pinfunction "CSI_D4/SDC2_CMD_168") (pintype "bidirectional"))
    )
    (net (code "71") (name "unconnected-(U1C-CSI_D5{slash}SDC2_CLK-Pad167)") (class "Default")
      (node (ref "U1") (pin "167") (pinfunction "CSI_D5/SDC2_CLK_167") (pintype "bidirectional"))
    )
    (net (code "72") (name "unconnected-(U1C-CSI_D6{slash}UART1_TX-Pad166)") (class "Default")
      (node (ref "U1") (pin "166") (pinfunction "CSI_D6/UART1_TX_166") (pintype "bidirectional"))
    )
    (net (code "73") (name "unconnected-(U1C-CSI_D7{slash}UART1_RX-Pad165)") (class "Default")
      (node (ref "U1") (pin "165") (pinfunction "CSI_D7/UART1_RX_165") (pintype "bidirectional"))
    )
    (net (code "74") (name "unconnected-(U1C-CSI_HSYNC{slash}SPI2_MOSI-Pad116)") (class "Default")
      (node (ref "U1") (pin "116") (pinfunction "CSI_HSYNC/SPI2_MOSI_116") (pintype "bidirectional"))
    )
    (net (code "75") (name "unconnected-(U1C-CSI_MCLK{slash}SPI2_CLK{slash}EINT15-Pad115)") (class "Default")
      (node (ref "U1") (pin "115") (pinfunction "CSI_MCLK/SPI2_CLK/EINT15_115") (pintype "bidirectional"))
    )
    (net (code "76") (name "unconnected-(U1C-CSI_PCLK{slash}SPI2_CS0{slash}EINT14-Pad114)") (class "Default")
      (node (ref "U1") (pin "114") (pinfunction "CSI_PCLK/SPI2_CS0/EINT14_114") (pintype "bidirectional"))
    )
    (net (code "77") (name "unconnected-(U1C-CSI_VSYNC{slash}SPI2_MISO-Pad117)") (class "Default")
      (node (ref "U1") (pin "117") (pinfunction "CSI_VSYNC/SPI2_MISO_117") (pintype "bidirectional"))
    )
    (net (code "78") (name "unconnected-(U1E-~{ALE}{slash}SPI0_MISO-Pad7)") (class "Default")
      (node (ref "U1") (pin "7") (pinfunction "~{ALE}/SPI0_MISO_7") (pintype "bidirectional"))
    )
    (net (code "79") (name "unconnected-(U1E-~{CE0}-Pad2)") (class "Default")
      (node (ref "U1") (pin "2") (pinfunction "~{CE0}_2") (pintype "bidirectional"))
    )
    (net (code "80") (name "unconnected-(U1E-~{CE1}{slash}SPI0_CS0-Pad3)") (class "Default")
      (node (ref "U1") (pin "3") (pinfunction "~{CE1}/SPI0_CS0_3") (pintype "bidirectional"))
    )
    (net (code "81") (name "unconnected-(U1E-~{CLE}{slash}SPI0_CLK-Pad6)") (class "Default")
      (node (ref "U1") (pin "6") (pinfunction "~{CLE}/SPI0_CLK_6") (pintype "bidirectional"))
    )
    (net (code "82") (name "unconnected-(U1E-~{DQ0}{slash}SDC2_D0-Pad118)") (class "Default")
      (node (ref "U1") (pin "118") (pinfunction "~{DQ0}/SDC2_D0_118") (pintype "bidirectional"))
    )
    (net (code "83") (name "unconnected-(U1E-~{DQ1}{slash}SDC2_D1-Pad119)") (class "Default")
      (node (ref "U1") (pin "119") (pinfunction "~{DQ1}/SDC2_D1_119") (pintype "bidirectional"))
    )
    (net (code "84") (name "unconnected-(U1E-~{DQ2}{slash}SDC2_D2-Pad120)") (class "Default")
      (node (ref "U1") (pin "120") (pinfunction "~{DQ2}/SDC2_D2_120") (pintype "bidirectional"))
    )
    (net (code "85") (name "unconnected-(U1E-~{DQ3}{slash}SDC2_D3-Pad121)") (class "Default")
      (node (ref "U1") (pin "121") (pinfunction "~{DQ3}/SDC2_D3_121") (pintype "bidirectional"))
    )
    (net (code "86") (name "unconnected-(U1E-~{DQ4}{slash}SDC2_D4-Pad122)") (class "Default")
      (node (ref "U1") (pin "122") (pinfunction "~{DQ4}/SDC2_D4_122") (pintype "bidirectional"))
    )
    (net (code "87") (name "unconnected-(U1E-~{DQ5}{slash}SDC2_D5-Pad123)") (class "Default")
      (node (ref "U1") (pin "123") (pinfunction "~{DQ5}/SDC2_D5_123") (pintype "bidirectional"))
    )
    (net (code "88") (name "unconnected-(U1E-~{DQ6}{slash}SDC2_D6-Pad124)") (class "Default")
      (node (ref "U1") (pin "124") (pinfunction "~{DQ6}/SDC2_D6_124") (pintype "bidirectional"))
    )
    (net (code "89") (name "unconnected-(U1E-~{DQ7}{slash}SDC2_D7-Pad125)") (class "Default")
      (node (ref "U1") (pin "125") (pinfunction "~{DQ7}/SDC2_D7_125") (pintype "bidirectional"))
    )
    (net (code "90") (name "unconnected-(U1E-~{QDS}-Pad162)") (class "Default")
      (node (ref "U1") (pin "162") (pinfunction "~{QDS}_162") (pintype "bidirectional"))
    )
    (net (code "91") (name "unconnected-(U1E-~{RB0}{slash}SDC2_CMD-Pad176)") (class "Default")
      (node (ref "U1") (pin "176") (pinfunction "~{RB0}/SDC2_CMD_176") (pintype "bidirectional"))
    )
    (net (code "92") (name "unconnected-(U1E-~{RB1}{slash}SDC2_CLK-Pad175)") (class "Default")
      (node (ref "U1") (pin "175") (pinfunction "~{RB1}/SDC2_CLK_175") (pintype "bidirectional"))
    )
    (net (code "93") (name "unconnected-(U1E-~{RE}-Pad1)") (class "Default")
      (node (ref "U1") (pin "1") (pinfunction "~{RE}_1") (pintype "bidirectional"))
    )
    (net (code "94") (name "unconnected-(U1E-~{WE}{slash}SPI0_MOSI-Pad8)") (class "Default")
      (node (ref "U1") (pin "8") (pinfunction "~{WE}/SPI0_MOSI_8") (pintype "bidirectional"))
    )
    (net (code "95") (name "unconnected-(U1F-TPX1-Pad89)") (class "Default")
      (node (ref "U1") (pin "89") (pinfunction "TPX1_89") (pintype "bidirectional"))
    )
    (net (code "96") (name "unconnected-(U1F-TPX2-Pad87)") (class "Default")
      (node (ref "U1") (pin "87") (pinfunction "TPX2_87") (pintype "bidirectional"))
    )
    (net (code "97") (name "unconnected-(U1F-TPY1-Pad90)") (class "Default")
      (node (ref "U1") (pin "90") (pinfunction "TPY1_90") (pintype "bidirectional"))
    )
    (net (code "98") (name "unconnected-(U1F-TPY2-Pad88)") (class "Default")
      (node (ref "U1") (pin "88") (pinfunction "TPY2_88") (pintype "bidirectional"))
    )
    (net (code "99") (name "unconnected-(U1G-TWI0_SCK-Pad101)") (class "Default")
      (node (ref "U1") (pin "101") (pinfunction "TWI0_SCK_101") (pintype "bidirectional"))
    )
    (net (code "100") (name "unconnected-(U1G-TWI0_SDA-Pad102)") (class "Default")
      (node (ref "U1") (pin "102") (pinfunction "TWI0_SDA_102") (pintype "bidirectional"))
    )
    (net (code "101") (name "unconnected-(U1I-DZQ-Pad17)") (class "Default")
      (node (ref "U1") (pin "17") (pinfunction "DZQ_17") (pintype "bidirectional"))
    )
    (net (code "102") (name "unconnected-(U1I-PB2{slash}EINT16-Pad103)") (class "Default")
      (node (ref "U1") (pin "103") (pinfunction "PB2/EINT16_103") (pintype "bidirectional"))
    )
    (net (code "103") (name "unconnected-(U1I-PB3{slash}EINT17-Pad150)") (class "Default")
      (node (ref "U1") (pin "150") (pinfunction "PB3/EINT17_150") (pintype "bidirectional"))
    )
    (net (code "104") (name "unconnected-(U1I-PB4{slash}EINT18-Pad104)") (class "Default")
      (node (ref "U1") (pin "104") (pinfunction "PB4/EINT18_104") (pintype "bidirectional"))
    )
    (net (code "105") (name "unconnected-(U1I-PB10{slash}EINT24-Pad10)") (class "Default")
      (node (ref "U1") (pin "10") (pinfunction "PB10/EINT24_10") (pintype "bidirectional"))
    )
    (net (code "106") (name "unconnected-(U1I-PB15-Pad105)") (class "Default")
      (node (ref "U1") (pin "105") (pinfunction "PB15_105") (pintype "bidirectional"))
    )
    (net (code "107") (name "unconnected-(U1I-PB16-Pad106)") (class "Default")
      (node (ref "U1") (pin "106") (pinfunction "PB16_106") (pintype "bidirectional"))
    )
    (net (code "108") (name "unconnected-(U1I-PB17-Pad161)") (class "Default")
      (node (ref "U1") (pin "161") (pinfunction "PB17_161") (pintype "bidirectional"))
    )
    (net (code "109") (name "unconnected-(U1I-PB18-Pad160)") (class "Default")
      (node (ref "U1") (pin "160") (pinfunction "PB18_160") (pintype "bidirectional"))
    )
    (net (code "110") (name "unconnected-(U1I-PG0{slash}EINT0-Pad155)") (class "Default")
      (node (ref "U1") (pin "155") (pinfunction "PG0/EINT0_155") (pintype "bidirectional"))
    )
    (net (code "111") (name "unconnected-(U1I-PG1{slash}EINT1-Pad154)") (class "Default")
      (node (ref "U1") (pin "154") (pinfunction "PG1/EINT1_154") (pintype "bidirectional"))
    )
    (net (code "112") (name "unconnected-(U1I-PG2{slash}EINT2-Pad153)") (class "Default")
      (node (ref "U1") (pin "153") (pinfunction "PG2/EINT2_153") (pintype "bidirectional"))
    )
    (net (code "113") (name "unconnected-(U1I-PG3{slash}UART1_TX{slash}EINT3-Pad152)") (class "Default")
      (node (ref "U1") (pin "152") (pinfunction "PG3/UART1_TX/EINT3_152") (pintype "bidirectional"))
    )
    (net (code "114") (name "unconnected-(U1I-PG4{slash}UART1_RX{slash}EINT4-Pad151)") (class "Default")
      (node (ref "U1") (pin "151") (pinfunction "PG4/UART1_RX/EINT4_151") (pintype "bidirectional"))
    )
    (net (code "115") (name "unconnected-(U1I-PG9{slash}SPI1_CS0{slash}UART3_TX{slash}EINT9-Pad12)") (class "Default")
      (node (ref "U1") (pin "12") (pinfunction "PG9/SPI1_CS0/UART3_TX/EINT9_12") (pintype "bidirectional"))
    )
    (net (code "116") (name "unconnected-(U1I-PG10{slash}SPI1_CLK{slash}UART3_RX{slash}EINT10-Pad13)") (class "Default")
      (node (ref "U1") (pin "13") (pinfunction "PG10/SPI1_CLK/UART3_RX/EINT10_13") (pintype "bidirectional"))
    )
    (net (code "117") (name "unconnected-(U1I-PG11{slash}SPI1_MOSI{slash}UART3_CTS{slash}EINT11-Pad14)") (class "Default")
      (node (ref "U1") (pin "14") (pinfunction "PG11/SPI1_MOSI/UART3_CTS/EINT11_14") (pintype "bidirectional"))
    )
    (net (code "118") (name "unconnected-(U1I-PG12{slash}SPI1_MISO{slash}UART3_RTS{slash}EINT12-Pad15)") (class "Default")
      (node (ref "U1") (pin "15") (pinfunction "PG12/SPI1_MISO/UART3_RTS/EINT12_15") (pintype "bidirectional"))
    )
    (net (code "119") (name "unconnected-(U1I-SVREF-Pad18)") (class "Default")
      (node (ref "U1") (pin "18") (pinfunction "SVREF_18") (pintype "bidirectional"))
    )
    (net (code "120") (name "unconnected-(U1J-SDC0_CLK-Pad110)") (class "Default")
      (node (ref "U1") (pin "110") (pinfunction "SDC0_CLK_110") (pintype "bidirectional"))
    )
    (net (code "121") (name "unconnected-(U1J-SDC0_CMD-Pad111)") (class "Default")
      (node (ref "U1") (pin "111") (pinfunction "SDC0_CMD_111") (pintype "bidirectional"))
    )
    (net (code "122") (name "unconnected-(U1J-SDC0_D0-Pad108)") (class "Default")
      (node (ref "U1") (pin "108") (pinfunction "SDC0_D0_108") (pintype "bidirectional"))
    )
    (net (code "123") (name "unconnected-(U1J-SDC0_D1-Pad107)") (class "Default")
      (node (ref "U1") (pin "107") (pinfunction "SDC0_D1_107") (pintype "bidirectional"))
    )
    (net (code "124") (name "unconnected-(U1J-SDC0_D2-Pad113)") (class "Default")
      (node (ref "U1") (pin "113") (pinfunction "SDC0_D2_113") (pintype "bidirectional"))
    )
    (net (code "125") (name "unconnected-(U1J-SDC0_D3-Pad112)") (class "Default")
      (node (ref "U1") (pin "112") (pinfunction "SDC0_D3_112") (pintype "bidirectional"))
    )
    (net (code "126") (name "unconnected-(U1M-D1+-Pad96)") (class "Default")
      (node (ref "U1") (pin "96") (pinfunction "D1+_96") (pintype "bidirectional"))
    )
    (net (code "127") (name "unconnected-(U1M-D1--Pad95)") (class "Default")
      (node (ref "U1") (pin "95") (pinfunction "D1-_95") (pintype "bidirectional"))
    )
    (net (code "128") (name "unconnected-(U1N-D0+-Pad94)") (class "Default")
      (node (ref "U1") (pin "94") (pinfunction "D0+_94") (pintype "bidirectional"))
    )
    (net (code "129") (name "unconnected-(U1N-D0--Pad93)") (class "Default")
      (node (ref "U1") (pin "93") (pinfunction "D0-_93") (pintype "bidirectional"))
    )
  )
)
